# Signal_bizard.net
KiCad netlist of a schematic drawn in Altium Designer
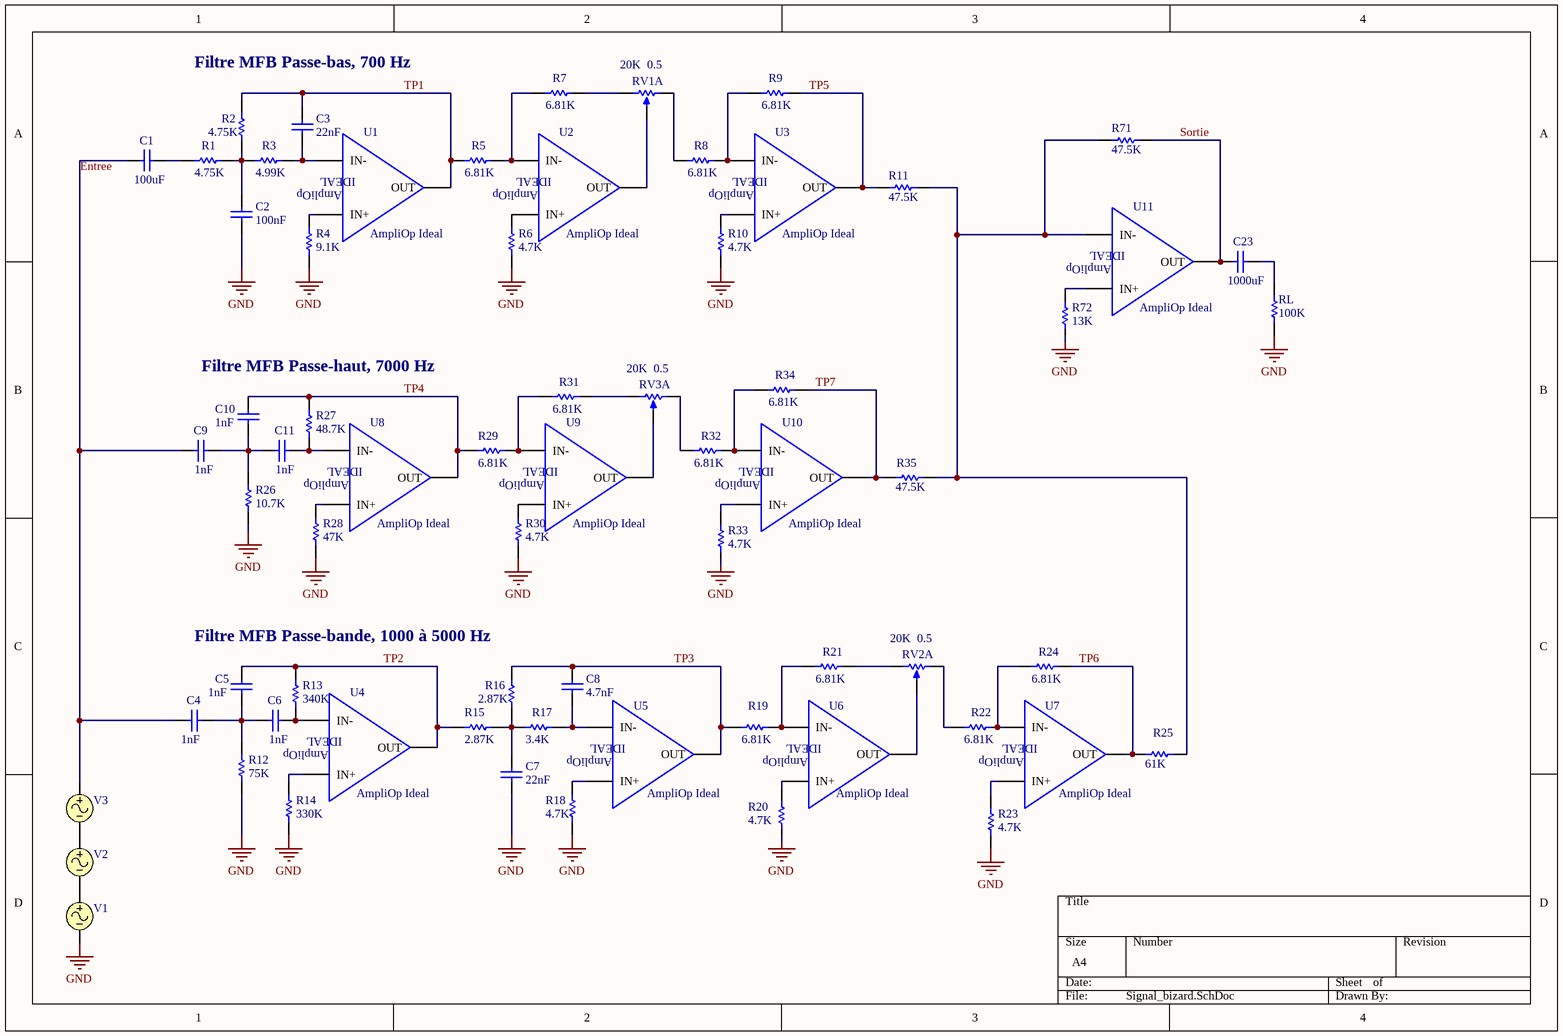
[diagram p0: Signal_bizard.SchDoc]

(export (version "E")
  (design (tool "Eeschema 10.0.6"))
  (components
    (comp (ref "C1")
      (value "100uF")
      (footprint "RAD-0.3")
      (description "Capacitor")
      (fields (field (name "Comment") "Cap") (field (name "PUBLISHER") "Altium Limited"))
      (libsource (lib "Miscellaneous Devices") (part "Cap"))
    )
    (comp (ref "C2")
      (value "100nF")
      (footprint "RAD-0.3")
      (description "Capacitor")
      (fields (field (name "Comment") "Cap") (field (name "PUBLISHER") "Altium Limited"))
      (libsource (lib "Miscellaneous Devices") (part "Cap"))
    )
    (comp (ref "C3")
      (value "22nF")
      (footprint "RAD-0.3")
      (description "Capacitor")
      (fields (field (name "Comment") "Cap") (field (name "PUBLISHER") "Altium Limited"))
      (libsource (lib "Miscellaneous Devices") (part "Cap"))
    )
    (comp (ref "C4")
      (value "1nF")
      (footprint "RAD-0.3")
      (description "Capacitor")
      (fields (field (name "Comment") "Cap") (field (name "PUBLISHER") "Altium Limited"))
      (libsource (lib "Miscellaneous Devices") (part "Cap"))
    )
    (comp (ref "C5")
      (value "1nF")
      (footprint "RAD-0.3")
      (description "Capacitor")
      (fields (field (name "Comment") "Cap") (field (name "PUBLISHER") "Altium Limited"))
      (libsource (lib "Miscellaneous Devices") (part "Cap"))
    )
    (comp (ref "C6")
      (value "1nF")
      (footprint "RAD-0.3")
      (description "Capacitor")
      (fields (field (name "Comment") "Cap") (field (name "PUBLISHER") "Altium Limited"))
      (libsource (lib "Miscellaneous Devices") (part "Cap"))
    )
    (comp (ref "C7")
      (value "22nF")
      (footprint "RAD-0.3")
      (description "Capacitor")
      (fields (field (name "Comment") "Cap") (field (name "PUBLISHER") "Altium Limited"))
      (libsource (lib "Miscellaneous Devices") (part "Cap"))
    )
    (comp (ref "C8")
      (value "4.7nF")
      (footprint "RAD-0.3")
      (description "Capacitor")
      (fields (field (name "Comment") "Cap") (field (name "PUBLISHER") "Altium Limited"))
      (libsource (lib "Miscellaneous Devices") (part "Cap"))
    )
    (comp (ref "C9")
      (value "1nF")
      (footprint "RAD-0.3")
      (description "Capacitor")
      (fields (field (name "Comment") "Cap") (field (name "PUBLISHER") "Altium Limited"))
      (libsource (lib "Miscellaneous Devices") (part "Cap"))
    )
    (comp (ref "C10")
      (value "1nF")
      (footprint "RAD-0.3")
      (description "Capacitor")
      (fields (field (name "Comment") "Cap") (field (name "PUBLISHER") "Altium Limited"))
      (libsource (lib "Miscellaneous Devices") (part "Cap"))
    )
    (comp (ref "C11")
      (value "1nF")
      (footprint "RAD-0.3")
      (description "Capacitor")
      (fields (field (name "Comment") "Cap") (field (name "PUBLISHER") "Altium Limited"))
      (libsource (lib "Miscellaneous Devices") (part "Cap"))
    )
    (comp (ref "C23")
      (value "1000uF")
      (footprint "RAD-0.3")
      (description "Capacitor")
      (fields (field (name "Comment") "Cap") (field (name "PUBLISHER") "Altium Limited"))
      (libsource (lib "Miscellaneous Devices") (part "Cap"))
    )
    (comp (ref "R1")
      (value "4.75K")
      (footprint "AXIAL-0.3")
      (description "Resistor")
      (fields (field (name "Comment") "Res1") (field (name "PUBLISHER") "Altium Limited"))
      (libsource (lib "Miscellaneous Devices") (part "Res1"))
    )
    (comp (ref "R2")
      (value "4.75K")
      (footprint "AXIAL-0.3")
      (description "Resistor")
      (fields (field (name "Comment") "Res1") (field (name "PUBLISHER") "Altium Limited"))
      (libsource (lib "Miscellaneous Devices") (part "Res1"))
    )
    (comp (ref "R3")
      (value "4.99K")
      (footprint "AXIAL-0.3")
      (description "Resistor")
      (fields (field (name "Comment") "Res1") (field (name "PUBLISHER") "Altium Limited"))
      (libsource (lib "Miscellaneous Devices") (part "Res1"))
    )
    (comp (ref "R4")
      (value "9.1K")
      (footprint "AXIAL-0.3")
      (description "Resistor")
      (fields (field (name "Comment") "Res1") (field (name "PUBLISHER") "Altium Limited"))
      (libsource (lib "Miscellaneous Devices") (part "Res1"))
    )
    (comp (ref "R5")
      (value "6.81K")
      (footprint "AXIAL-0.3")
      (description "Resistor")
      (fields (field (name "Comment") "Res1") (field (name "PUBLISHER") "Altium Limited"))
      (libsource (lib "Miscellaneous Devices") (part "Res1"))
    )
    (comp (ref "R6")
      (value "4.7K")
      (footprint "AXIAL-0.3")
      (description "Resistor")
      (fields (field (name "Comment") "Res1") (field (name "PUBLISHER") "Altium Limited"))
      (libsource (lib "Miscellaneous Devices") (part "Res1"))
    )
    (comp (ref "R7")
      (value "6.81K")
      (footprint "AXIAL-0.3")
      (description "Resistor")
      (fields (field (name "Comment") "Res1") (field (name "PUBLISHER") "Altium Limited"))
      (libsource (lib "Miscellaneous Devices") (part "Res1"))
    )
    (comp (ref "R8")
      (value "6.81K")
      (footprint "AXIAL-0.3")
      (description "Resistor")
      (fields (field (name "Comment") "Res1") (field (name "PUBLISHER") "Altium Limited"))
      (libsource (lib "Miscellaneous Devices") (part "Res1"))
    )
    (comp (ref "R9")
      (value "6.81K")
      (footprint "AXIAL-0.3")
      (description "Resistor")
      (fields (field (name "Comment") "Res1") (field (name "PUBLISHER") "Altium Limited"))
      (libsource (lib "Miscellaneous Devices") (part "Res1"))
    )
    (comp (ref "R10")
      (value "4.7K")
      (footprint "AXIAL-0.3")
      (description "Resistor")
      (fields (field (name "Comment") "Res1") (field (name "PUBLISHER") "Altium Limited"))
      (libsource (lib "Miscellaneous Devices") (part "Res1"))
    )
    (comp (ref "R11")
      (value "47.5K")
      (footprint "AXIAL-0.3")
      (description "Resistor")
      (fields (field (name "Comment") "Res1") (field (name "PUBLISHER") "Altium Limited"))
      (libsource (lib "Miscellaneous Devices") (part "Res1"))
    )
    (comp (ref "R12")
      (value "75K")
      (footprint "AXIAL-0.3")
      (description "Resistor")
      (fields (field (name "Comment") "Res1") (field (name "PUBLISHER") "Altium Limited"))
      (libsource (lib "Miscellaneous Devices") (part "Res1"))
    )
    (comp (ref "R13")
      (value "340K")
      (footprint "AXIAL-0.3")
      (description "Resistor")
      (fields (field (name "Comment") "Res1") (field (name "PUBLISHER") "Altium Limited"))
      (libsource (lib "Miscellaneous Devices") (part "Res1"))
    )
    (comp (ref "R14")
      (value "330K")
      (footprint "AXIAL-0.3")
      (description "Resistor")
      (fields (field (name "Comment") "Res1") (field (name "PUBLISHER") "Altium Limited"))
      (libsource (lib "Miscellaneous Devices") (part "Res1"))
    )
    (comp (ref "R15")
      (value "2.87K")
      (footprint "AXIAL-0.3")
      (description "Resistor")
      (fields (field (name "Comment") "Res1") (field (name "PUBLISHER") "Altium Limited"))
      (libsource (lib "Miscellaneous Devices") (part "Res1"))
    )
    (comp (ref "R16")
      (value "2.87K")
      (footprint "AXIAL-0.3")
      (description "Resistor")
      (fields (field (name "Comment") "Res1") (field (name "PUBLISHER") "Altium Limited"))
      (libsource (lib "Miscellaneous Devices") (part "Res1"))
    )
    (comp (ref "R17")
      (value "3.4K")
      (footprint "AXIAL-0.3")
      (description "Resistor")
      (fields (field (name "Comment") "Res1") (field (name "PUBLISHER") "Altium Limited"))
      (libsource (lib "Miscellaneous Devices") (part "Res1"))
    )
    (comp (ref "R18")
      (value "4.7K")
      (footprint "AXIAL-0.3")
      (description "Resistor")
      (fields (field (name "Comment") "Res1") (field (name "PUBLISHER") "Altium Limited"))
      (libsource (lib "Miscellaneous Devices") (part "Res1"))
    )
    (comp (ref "R19")
      (value "6.81K")
      (footprint "AXIAL-0.3")
      (description "Resistor")
      (fields (field (name "Comment") "Res1") (field (name "PUBLISHER") "Altium Limited"))
      (libsource (lib "Miscellaneous Devices") (part "Res1"))
    )
    (comp (ref "R20")
      (value "4.7K")
      (footprint "AXIAL-0.3")
      (description "Resistor")
      (fields (field (name "Comment") "Res1") (field (name "PUBLISHER") "Altium Limited"))
      (libsource (lib "Miscellaneous Devices") (part "Res1"))
    )
    (comp (ref "R21")
      (value "6.81K")
      (footprint "AXIAL-0.3")
      (description "Resistor")
      (fields (field (name "Comment") "Res1") (field (name "PUBLISHER") "Altium Limited"))
      (libsource (lib "Miscellaneous Devices") (part "Res1"))
    )
    (comp (ref "R22")
      (value "6.81K")
      (footprint "AXIAL-0.3")
      (description "Resistor")
      (fields (field (name "Comment") "Res1") (field (name "PUBLISHER") "Altium Limited"))
      (libsource (lib "Miscellaneous Devices") (part "Res1"))
    )
    (comp (ref "R23")
      (value "4.7K")
      (footprint "AXIAL-0.3")
      (description "Resistor")
      (fields (field (name "Comment") "Res1") (field (name "PUBLISHER") "Altium Limited"))
      (libsource (lib "Miscellaneous Devices") (part "Res1"))
    )
    (comp (ref "R24")
      (value "6.81K")
      (footprint "AXIAL-0.3")
      (description "Resistor")
      (fields (field (name "Comment") "Res1") (field (name "PUBLISHER") "Altium Limited"))
      (libsource (lib "Miscellaneous Devices") (part "Res1"))
    )
    (comp (ref "R25")
      (value "61K")
      (footprint "AXIAL-0.3")
      (description "Resistor")
      (fields (field (name "Comment") "Res1") (field (name "PUBLISHER") "Altium Limited"))
      (libsource (lib "Miscellaneous Devices") (part "Res1"))
    )
    (comp (ref "R26")
      (value "10.7K")
      (footprint "AXIAL-0.3")
      (description "Resistor")
      (fields (field (name "Comment") "Res1") (field (name "PUBLISHER") "Altium Limited"))
      (libsource (lib "Miscellaneous Devices") (part "Res1"))
    )
    (comp (ref "R27")
      (value "48.7K")
      (footprint "AXIAL-0.3")
      (description "Resistor")
      (fields (field (name "Comment") "Res1") (field (name "PUBLISHER") "Altium Limited"))
      (libsource (lib "Miscellaneous Devices") (part "Res1"))
    )
    (comp (ref "R28")
      (value "47K")
      (footprint "AXIAL-0.3")
      (description "Resistor")
      (fields (field (name "Comment") "Res1") (field (name "PUBLISHER") "Altium Limited"))
      (libsource (lib "Miscellaneous Devices") (part "Res1"))
    )
    (comp (ref "R29")
      (value "6.81K")
      (footprint "AXIAL-0.3")
      (description "Resistor")
      (fields (field (name "Comment") "Res1") (field (name "PUBLISHER") "Altium Limited"))
      (libsource (lib "Miscellaneous Devices") (part "Res1"))
    )
    (comp (ref "R30")
      (value "4.7K")
      (footprint "AXIAL-0.3")
      (description "Resistor")
      (fields (field (name "Comment") "Res1") (field (name "PUBLISHER") "Altium Limited"))
      (libsource (lib "Miscellaneous Devices") (part "Res1"))
    )
    (comp (ref "R31")
      (value "6.81K")
      (footprint "AXIAL-0.3")
      (description "Resistor")
      (fields (field (name "Comment") "Res1") (field (name "PUBLISHER") "Altium Limited"))
      (libsource (lib "Miscellaneous Devices") (part "Res1"))
    )
    (comp (ref "R32")
      (value "6.81K")
      (footprint "AXIAL-0.3")
      (description "Resistor")
      (fields (field (name "Comment") "Res1") (field (name "PUBLISHER") "Altium Limited"))
      (libsource (lib "Miscellaneous Devices") (part "Res1"))
    )
    (comp (ref "R33")
      (value "4.7K")
      (footprint "AXIAL-0.3")
      (description "Resistor")
      (fields (field (name "Comment") "Res1") (field (name "PUBLISHER") "Altium Limited"))
      (libsource (lib "Miscellaneous Devices") (part "Res1"))
    )
    (comp (ref "R34")
      (value "6.81K")
      (footprint "AXIAL-0.3")
      (description "Resistor")
      (fields (field (name "Comment") "Res1") (field (name "PUBLISHER") "Altium Limited"))
      (libsource (lib "Miscellaneous Devices") (part "Res1"))
    )
    (comp (ref "R35")
      (value "47.5K")
      (footprint "AXIAL-0.3")
      (description "Resistor")
      (fields (field (name "Comment") "Res1") (field (name "PUBLISHER") "Altium Limited"))
      (libsource (lib "Miscellaneous Devices") (part "Res1"))
    )
    (comp (ref "R71")
      (value "47.5K")
      (footprint "AXIAL-0.3")
      (description "Resistor")
      (fields (field (name "Comment") "Res1") (field (name "PUBLISHER") "Altium Limited"))
      (libsource (lib "Miscellaneous Devices") (part "Res1"))
    )
    (comp (ref "R72")
      (value "13K")
      (footprint "AXIAL-0.3")
      (description "Resistor")
      (fields (field (name "Comment") "Res1") (field (name "PUBLISHER") "Altium Limited"))
      (libsource (lib "Miscellaneous Devices") (part "Res1"))
    )
    (comp (ref "RL")
      (value "100K")
      (footprint "AXIAL-0.3")
      (description "Resistor")
      (fields (field (name "Comment") "Res1") (field (name "PUBLISHER") "Altium Limited"))
      (libsource (lib "Miscellaneous Devices") (part "Res1"))
    )
    (comp (ref "RV1A")
      (value "20K")
      (footprint "VR5")
      (description "Potentiometer")
      (fields
        (field (name "SET POSITION") "0.5")
        (field (name "Comment") "RPot")
        (field (name "PUBLISHER") "Altium Limited")
      )
      (libsource (lib "Miscellaneous Devices") (part "RPot"))
    )
    (comp (ref "RV2A")
      (value "20K")
      (footprint "VR5")
      (description "Potentiometer")
      (fields
        (field (name "SET POSITION") "0.5")
        (field (name "Comment") "RPot")
        (field (name "PUBLISHER") "Altium Limited")
      )
      (libsource (lib "Miscellaneous Devices") (part "RPot"))
    )
    (comp (ref "RV3A")
      (value "20K")
      (footprint "VR5")
      (description "Potentiometer")
      (fields
        (field (name "SET POSITION") "0.5")
        (field (name "Comment") "RPot")
        (field (name "PUBLISHER") "Altium Limited")
      )
      (libsource (lib "Miscellaneous Devices") (part "RPot"))
    )
    (comp (ref "U1") (value "AmpliOp Ideal") (libsource (lib "Librarie_S2") (part "AmpliOp_ideal")))
    (comp (ref "U2") (value "AmpliOp Ideal") (libsource (lib "Librarie_S2") (part "AmpliOp_ideal")))
    (comp (ref "U3") (value "AmpliOp Ideal") (libsource (lib "Librarie_S2") (part "AmpliOp_ideal")))
    (comp (ref "U4") (value "AmpliOp Ideal") (libsource (lib "Librarie_S2") (part "AmpliOp_ideal")))
    (comp (ref "U5") (value "AmpliOp Ideal") (libsource (lib "Librarie_S2") (part "AmpliOp_ideal")))
    (comp (ref "U6") (value "AmpliOp Ideal") (libsource (lib "Librarie_S2") (part "AmpliOp_ideal")))
    (comp (ref "U7") (value "AmpliOp Ideal") (libsource (lib "Librarie_S2") (part "AmpliOp_ideal")))
    (comp (ref "U8") (value "AmpliOp Ideal") (libsource (lib "Librarie_S2") (part "AmpliOp_ideal")))
    (comp (ref "U9") (value "AmpliOp Ideal") (libsource (lib "Librarie_S2") (part "AmpliOp_ideal")))
    (comp (ref "U10") (value "AmpliOp Ideal") (libsource (lib "Librarie_S2") (part "AmpliOp_ideal")))
    (comp (ref "U11") (value "AmpliOp Ideal") (libsource (lib "Librarie_S2") (part "AmpliOp_ideal")))
    (comp (ref "V1")
      (value "SIN(0 0.25 15000 0 0 0)")
      (description "Sinusoidal Voltage Source")
      (fields (field (name "PUBLISHER") "Altium Limited"))
      (libsource (lib "Simulation Sources") (part "VSIN"))
    )
    (comp (ref "V2")
      (value "SIN(0 0.25 2500 0 0 0)")
      (description "Sinusoidal Voltage Source")
      (fields (field (name "PUBLISHER") "Altium Limited"))
      (libsource (lib "Simulation Sources") (part "VSIN"))
    )
    (comp (ref "V3")
      (value "SIN(0 0.25 300 0 0 0)")
      (description "Sinusoidal Voltage Source")
      (fields (field (name "PUBLISHER") "Altium Limited"))
      (libsource (lib "Simulation Sources") (part "VSIN"))
    )
  )
  (nets
    (net (code "1") (name "/Entree") (class "Default")
      (node (ref "C1") (pin "1") (pinfunction "1_1") (pintype "passive"))
      (node (ref "C4") (pin "1") (pinfunction "1_1") (pintype "passive"))
      (node (ref "C9") (pin "1") (pinfunction "1_1") (pintype "passive"))
      (node (ref "V3") (pin "1") (pinfunction "1_1") (pintype "passive"))
    )
    (net (code "2") (name "/Sortie") (class "Default")
      (node (ref "C23") (pin "1") (pinfunction "1_1") (pintype "passive"))
      (node (ref "R71") (pin "2") (pinfunction "2_2") (pintype "passive"))
      (node (ref "U11") (pin "3") (pinfunction "OUT_3") (pintype "passive"))
    )
    (net (code "3") (name "/TP1") (class "Default")
      (node (ref "C3") (pin "1") (pinfunction "1_1") (pintype "passive"))
      (node (ref "R2") (pin "1") (pinfunction "1_1") (pintype "passive"))
      (node (ref "R5") (pin "1") (pinfunction "1_1") (pintype "passive"))
      (node (ref "U1") (pin "3") (pinfunction "OUT_3") (pintype "passive"))
    )
    (net (code "4") (name "/TP2") (class "Default")
      (node (ref "C5") (pin "1") (pinfunction "1_1") (pintype "passive"))
      (node (ref "R13") (pin "1") (pinfunction "1_1") (pintype "passive"))
      (node (ref "R15") (pin "1") (pinfunction "1_1") (pintype "passive"))
      (node (ref "U4") (pin "3") (pinfunction "OUT_3") (pintype "passive"))
    )
    (net (code "5") (name "/TP3") (class "Default")
      (node (ref "C8") (pin "1") (pinfunction "1_1") (pintype "passive"))
      (node (ref "R16") (pin "1") (pinfunction "1_1") (pintype "passive"))
      (node (ref "R19") (pin "1") (pinfunction "1_1") (pintype "passive"))
      (node (ref "U5") (pin "3") (pinfunction "OUT_3") (pintype "passive"))
    )
    (net (code "6") (name "/TP4") (class "Default")
      (node (ref "C10") (pin "1") (pinfunction "1_1") (pintype "passive"))
      (node (ref "R27") (pin "1") (pinfunction "1_1") (pintype "passive"))
      (node (ref "R29") (pin "1") (pinfunction "1_1") (pintype "passive"))
      (node (ref "U8") (pin "3") (pinfunction "OUT_3") (pintype "passive"))
    )
    (net (code "7") (name "/TP5") (class "Default")
      (node (ref "R11") (pin "1") (pinfunction "1_1") (pintype "passive"))
      (node (ref "R9") (pin "2") (pinfunction "2_2") (pintype "passive"))
      (node (ref "U3") (pin "3") (pinfunction "OUT_3") (pintype "passive"))
    )
    (net (code "8") (name "/TP6") (class "Default")
      (node (ref "R24") (pin "2") (pinfunction "2_2") (pintype "passive"))
      (node (ref "R25") (pin "1") (pinfunction "1_1") (pintype "passive"))
      (node (ref "U7") (pin "3") (pinfunction "OUT_3") (pintype "passive"))
    )
    (net (code "9") (name "/TP7") (class "Default")
      (node (ref "R34") (pin "2") (pinfunction "2_2") (pintype "passive"))
      (node (ref "R35") (pin "1") (pinfunction "1_1") (pintype "passive"))
      (node (ref "U10") (pin "3") (pinfunction "OUT_3") (pintype "passive"))
    )
    (net (code "10") (name "GND") (class "Default")
      (node (ref "C2") (pin "2") (pinfunction "2_2") (pintype "passive"))
      (node (ref "C7") (pin "2") (pinfunction "2_2") (pintype "passive"))
      (node (ref "R10") (pin "2") (pinfunction "2_2") (pintype "passive"))
      (node (ref "R12") (pin "2") (pinfunction "2_2") (pintype "passive"))
      (node (ref "R14") (pin "2") (pinfunction "2_2") (pintype "passive"))
      (node (ref "R18") (pin "2") (pinfunction "2_2") (pintype "passive"))
      (node (ref "R20") (pin "2") (pinfunction "2_2") (pintype "passive"))
      (node (ref "R23") (pin "2") (pinfunction "2_2") (pintype "passive"))
      (node (ref "R26") (pin "2") (pinfunction "2_2") (pintype "passive"))
      (node (ref "R28") (pin "2") (pinfunction "2_2") (pintype "passive"))
      (node (ref "R30") (pin "2") (pinfunction "2_2") (pintype "passive"))
      (node (ref "R33") (pin "2") (pinfunction "2_2") (pintype "passive"))
      (node (ref "R4") (pin "2") (pinfunction "2_2") (pintype "passive"))
      (node (ref "R6") (pin "2") (pinfunction "2_2") (pintype "passive"))
      (node (ref "R72") (pin "2") (pinfunction "2_2") (pintype "passive"))
      (node (ref "RL") (pin "1") (pinfunction "1_1") (pintype "passive"))
      (node (ref "V1") (pin "2") (pinfunction "2_2") (pintype "passive"))
    )
    (net (code "11") (name "Net-(C1-Pad2)") (class "Default")
      (node (ref "C1") (pin "2") (pinfunction "2_2") (pintype "passive"))
      (node (ref "R1") (pin "1") (pinfunction "1_1") (pintype "passive"))
    )
    (net (code "12") (name "Net-(C2-Pad1)") (class "Default")
      (node (ref "C2") (pin "1") (pinfunction "1_1") (pintype "passive"))
      (node (ref "R1") (pin "2") (pinfunction "2_2") (pintype "passive"))
      (node (ref "R2") (pin "2") (pinfunction "2_2") (pintype "passive"))
      (node (ref "R3") (pin "1") (pinfunction "1_1") (pintype "passive"))
    )
    (net (code "13") (name "Net-(C4-Pad2)") (class "Default")
      (node (ref "C4") (pin "2") (pinfunction "2_2") (pintype "passive"))
      (node (ref "C5") (pin "2") (pinfunction "2_2") (pintype "passive"))
      (node (ref "C6") (pin "1") (pinfunction "1_1") (pintype "passive"))
      (node (ref "R12") (pin "1") (pinfunction "1_1") (pintype "passive"))
    )
    (net (code "14") (name "Net-(C7-Pad1)") (class "Default")
      (node (ref "C7") (pin "1") (pinfunction "1_1") (pintype "passive"))
      (node (ref "R15") (pin "2") (pinfunction "2_2") (pintype "passive"))
      (node (ref "R16") (pin "2") (pinfunction "2_2") (pintype "passive"))
      (node (ref "R17") (pin "1") (pinfunction "1_1") (pintype "passive"))
    )
    (net (code "15") (name "Net-(C10-Pad2)") (class "Default")
      (node (ref "C10") (pin "2") (pinfunction "2_2") (pintype "passive"))
      (node (ref "C11") (pin "1") (pinfunction "1_1") (pintype "passive"))
      (node (ref "C9") (pin "2") (pinfunction "2_2") (pintype "passive"))
      (node (ref "R26") (pin "1") (pinfunction "1_1") (pintype "passive"))
    )
    (net (code "16") (name "Net-(C23-Pad2)") (class "Default")
      (node (ref "C23") (pin "2") (pinfunction "2_2") (pintype "passive"))
      (node (ref "RL") (pin "2") (pinfunction "2_2") (pintype "passive"))
    )
    (net (code "17") (name "Net-(RV1A-BOT)") (class "Default")
      (node (ref "R8") (pin "1") (pinfunction "1_1") (pintype "passive"))
      (node (ref "RV1A") (pin "2") (pinfunction "BOT_2") (pintype "passive"))
    )
    (net (code "18") (name "Net-(RV1A-TAP)") (class "Default")
      (node (ref "RV1A") (pin "3") (pinfunction "TAP_3") (pintype "passive"))
      (node (ref "U2") (pin "3") (pinfunction "OUT_3") (pintype "passive"))
    )
    (net (code "19") (name "Net-(RV1A-TOP)") (class "Default")
      (node (ref "R7") (pin "2") (pinfunction "2_2") (pintype "passive"))
      (node (ref "RV1A") (pin "1") (pinfunction "TOP_1") (pintype "passive"))
    )
    (net (code "20") (name "Net-(RV2A-BOT)") (class "Default")
      (node (ref "R22") (pin "1") (pinfunction "1_1") (pintype "passive"))
      (node (ref "RV2A") (pin "2") (pinfunction "BOT_2") (pintype "passive"))
    )
    (net (code "21") (name "Net-(RV2A-TAP)") (class "Default")
      (node (ref "RV2A") (pin "3") (pinfunction "TAP_3") (pintype "passive"))
      (node (ref "U6") (pin "3") (pinfunction "OUT_3") (pintype "passive"))
    )
    (net (code "22") (name "Net-(RV2A-TOP)") (class "Default")
      (node (ref "R21") (pin "2") (pinfunction "2_2") (pintype "passive"))
      (node (ref "RV2A") (pin "1") (pinfunction "TOP_1") (pintype "passive"))
    )
    (net (code "23") (name "Net-(RV3A-BOT)") (class "Default")
      (node (ref "R32") (pin "1") (pinfunction "1_1") (pintype "passive"))
      (node (ref "RV3A") (pin "2") (pinfunction "BOT_2") (pintype "passive"))
    )
    (net (code "24") (name "Net-(RV3A-TAP)") (class "Default")
      (node (ref "RV3A") (pin "3") (pinfunction "TAP_3") (pintype "passive"))
      (node (ref "U9") (pin "3") (pinfunction "OUT_3") (pintype "passive"))
    )
    (net (code "25") (name "Net-(RV3A-TOP)") (class "Default")
      (node (ref "R31") (pin "2") (pinfunction "2_2") (pintype "passive"))
      (node (ref "RV3A") (pin "1") (pinfunction "TOP_1") (pintype "passive"))
    )
    (net (code "26") (name "Net-(U1-IN+)") (class "Default")
      (node (ref "R4") (pin "1") (pinfunction "1_1") (pintype "passive"))
      (node (ref "U1") (pin "1") (pinfunction "IN+_1") (pintype "passive"))
    )
    (net (code "27") (name "Net-(U1-IN-)") (class "Default")
      (node (ref "C3") (pin "2") (pinfunction "2_2") (pintype "passive"))
      (node (ref "R3") (pin "2") (pinfunction "2_2") (pintype "passive"))
      (node (ref "U1") (pin "2") (pinfunction "IN-_2") (pintype "passive"))
    )
    (net (code "28") (name "Net-(U2-IN+)") (class "Default")
      (node (ref "R6") (pin "1") (pinfunction "1_1") (pintype "passive"))
      (node (ref "U2") (pin "1") (pinfunction "IN+_1") (pintype "passive"))
    )
    (net (code "29") (name "Net-(U2-IN-)") (class "Default")
      (node (ref "R5") (pin "2") (pinfunction "2_2") (pintype "passive"))
      (node (ref "R7") (pin "1") (pinfunction "1_1") (pintype "passive"))
      (node (ref "U2") (pin "2") (pinfunction "IN-_2") (pintype "passive"))
    )
    (net (code "30") (name "Net-(U3-IN+)") (class "Default")
      (node (ref "R10") (pin "1") (pinfunction "1_1") (pintype "passive"))
      (node (ref "U3") (pin "1") (pinfunction "IN+_1") (pintype "passive"))
    )
    (net (code "31") (name "Net-(U3-IN-)") (class "Default")
      (node (ref "R8") (pin "2") (pinfunction "2_2") (pintype "passive"))
      (node (ref "R9") (pin "1") (pinfunction "1_1") (pintype "passive"))
      (node (ref "U3") (pin "2") (pinfunction "IN-_2") (pintype "passive"))
    )
    (net (code "32") (name "Net-(U4-IN+)") (class "Default")
      (node (ref "R14") (pin "1") (pinfunction "1_1") (pintype "passive"))
      (node (ref "U4") (pin "1") (pinfunction "IN+_1") (pintype "passive"))
    )
    (net (code "33") (name "Net-(U4-IN-)") (class "Default")
      (node (ref "C6") (pin "2") (pinfunction "2_2") (pintype "passive"))
      (node (ref "R13") (pin "2") (pinfunction "2_2") (pintype "passive"))
      (node (ref "U4") (pin "2") (pinfunction "IN-_2") (pintype "passive"))
    )
    (net (code "34") (name "Net-(U5-IN+)") (class "Default")
      (node (ref "R18") (pin "1") (pinfunction "1_1") (pintype "passive"))
      (node (ref "U5") (pin "1") (pinfunction "IN+_1") (pintype "passive"))
    )
    (net (code "35") (name "Net-(U5-IN-)") (class "Default")
      (node (ref "C8") (pin "2") (pinfunction "2_2") (pintype "passive"))
      (node (ref "R17") (pin "2") (pinfunction "2_2") (pintype "passive"))
      (node (ref "U5") (pin "2") (pinfunction "IN-_2") (pintype "passive"))
    )
    (net (code "36") (name "Net-(U6-IN+)") (class "Default")
      (node (ref "R20") (pin "1") (pinfunction "1_1") (pintype "passive"))
      (node (ref "U6") (pin "1") (pinfunction "IN+_1") (pintype "passive"))
    )
    (net (code "37") (name "Net-(U6-IN-)") (class "Default")
      (node (ref "R19") (pin "2") (pinfunction "2_2") (pintype "passive"))
      (node (ref "R21") (pin "1") (pinfunction "1_1") (pintype "passive"))
      (node (ref "U6") (pin "2") (pinfunction "IN-_2") (pintype "passive"))
    )
    (net (code "38") (name "Net-(U7-IN+)") (class "Default")
      (node (ref "R23") (pin "1") (pinfunction "1_1") (pintype "passive"))
      (node (ref "U7") (pin "1") (pinfunction "IN+_1") (pintype "passive"))
    )
    (net (code "39") (name "Net-(U7-IN-)") (class "Default")
      (node (ref "R22") (pin "2") (pinfunction "2_2") (pintype "passive"))
      (node (ref "R24") (pin "1") (pinfunction "1_1") (pintype "passive"))
      (node (ref "U7") (pin "2") (pinfunction "IN-_2") (pintype "passive"))
    )
    (net (code "40") (name "Net-(U8-IN+)") (class "Default")
      (node (ref "R28") (pin "1") (pinfunction "1_1") (pintype "passive"))
      (node (ref "U8") (pin "1") (pinfunction "IN+_1") (pintype "passive"))
    )
    (net (code "41") (name "Net-(U8-IN-)") (class "Default")
      (node (ref "C11") (pin "2") (pinfunction "2_2") (pintype "passive"))
      (node (ref "R27") (pin "2") (pinfunction "2_2") (pintype "passive"))
      (node (ref "U8") (pin "2") (pinfunction "IN-_2") (pintype "passive"))
    )
    (net (code "42") (name "Net-(U9-IN+)") (class "Default")
      (node (ref "R30") (pin "1") (pinfunction "1_1") (pintype "passive"))
      (node (ref "U9") (pin "1") (pinfunction "IN+_1") (pintype "passive"))
    )
    (net (code "43") (name "Net-(U9-IN-)") (class "Default")
      (node (ref "R29") (pin "2") (pinfunction "2_2") (pintype "passive"))
      (node (ref "R31") (pin "1") (pinfunction "1_1") (pintype "passive"))
      (node (ref "U9") (pin "2") (pinfunction "IN-_2") (pintype "passive"))
    )
    (net (code "44") (name "Net-(U10-IN+)") (class "Default")
      (node (ref "R33") (pin "1") (pinfunction "1_1") (pintype "passive"))
      (node (ref "U10") (pin "1") (pinfunction "IN+_1") (pintype "passive"))
    )
    (net (code "45") (name "Net-(U10-IN-)") (class "Default")
      (node (ref "R32") (pin "2") (pinfunction "2_2") (pintype "passive"))
      (node (ref "R34") (pin "1") (pinfunction "1_1") (pintype "passive"))
      (node (ref "U10") (pin "2") (pinfunction "IN-_2") (pintype "passive"))
    )
    (net (code "46") (name "Net-(U11-IN+)") (class "Default")
      (node (ref "R72") (pin "1") (pinfunction "1_1") (pintype "passive"))
      (node (ref "U11") (pin "1") (pinfunction "IN+_1") (pintype "passive"))
    )
    (net (code "47") (name "Net-(U11-IN-)") (class "Default")
      (node (ref "R11") (pin "2") (pinfunction "2_2") (pintype "passive"))
      (node (ref "R25") (pin "2") (pinfunction "2_2") (pintype "passive"))
      (node (ref "R35") (pin "2") (pinfunction "2_2") (pintype "passive"))
      (node (ref "R71") (pin "1") (pinfunction "1_1") (pintype "passive"))
      (node (ref "U11") (pin "2") (pinfunction "IN-_2") (pintype "passive"))
    )
    (net (code "48") (name "Net-(V1-Pad1)") (class "Default")
      (node (ref "V1") (pin "1") (pinfunction "1_1") (pintype "passive"))
      (node (ref "V2") (pin "2") (pinfunction "2_2") (pintype "passive"))
    )
    (net (code "49") (name "Net-(V2-Pad1)") (class "Default")
      (node (ref "V2") (pin "1") (pinfunction "1_1") (pintype "passive"))
      (node (ref "V3") (pin "2") (pinfunction "2_2") (pintype "passive"))
    )
  )
)
